# SignalBundling.net
KiCad netlist of a schematic drawn in Altium Designer
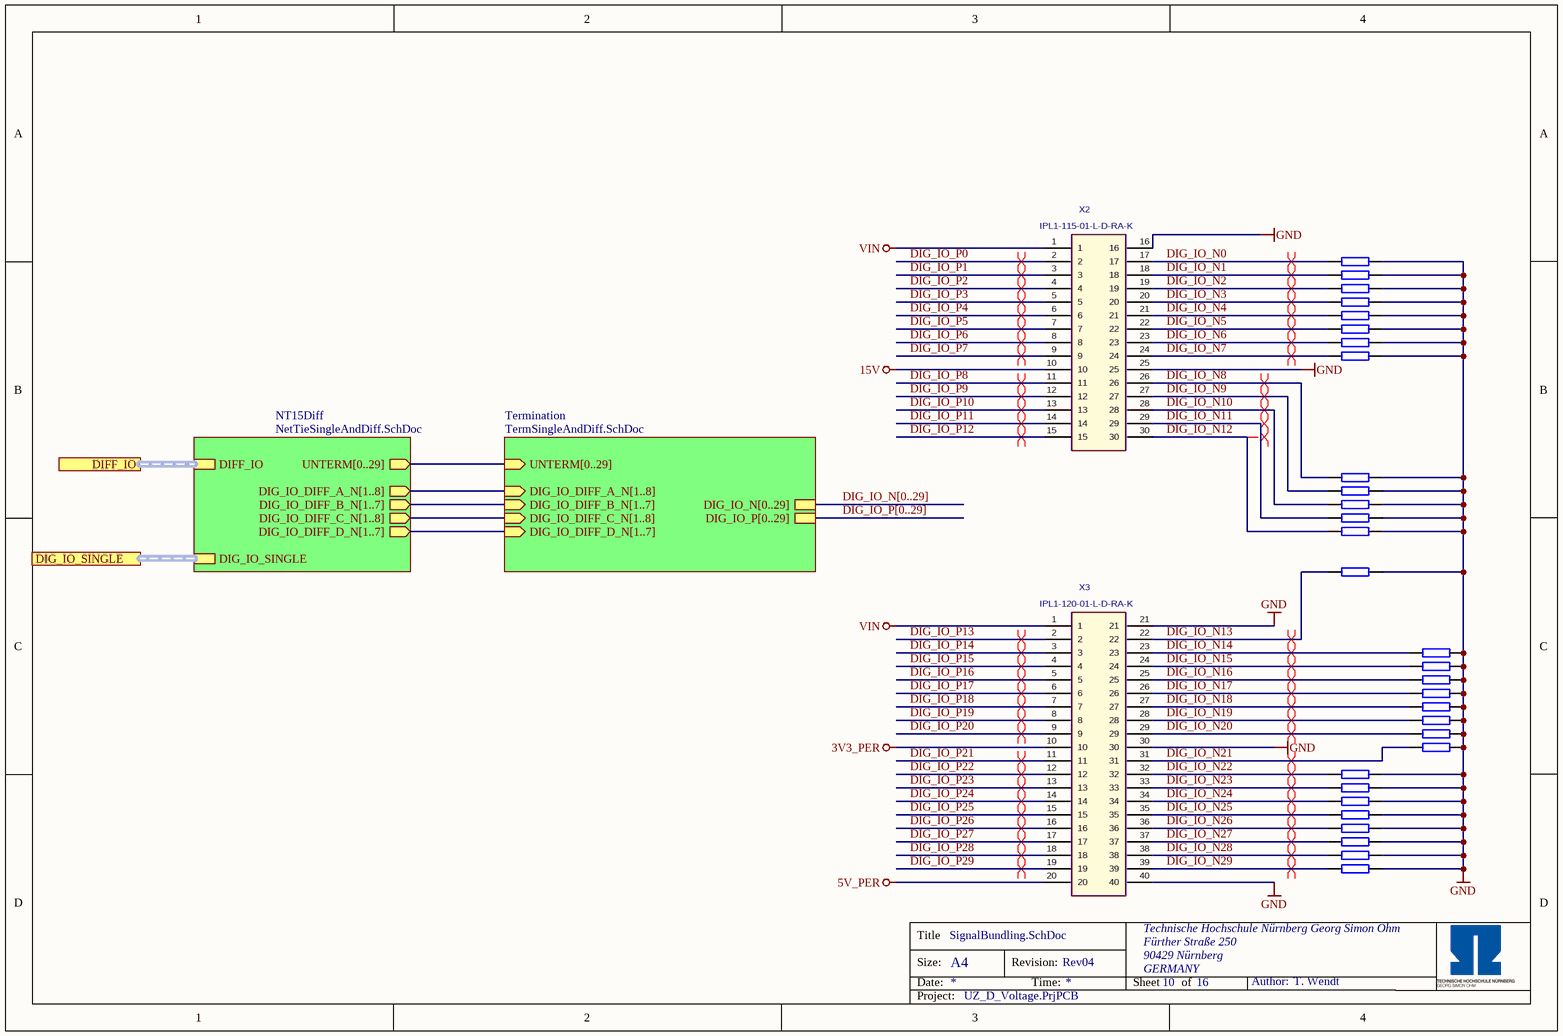
[diagram p0: SignalBundling.SchDoc]

(export (version "E")
  (design (tool "Eeschema 10.0.6"))
  (components
    (comp (ref "R21")
      (value "0R")
      (footprint "RES 0603_1608")
      (description "SMD resistor E24 series")
      (fields
        (field (name "MANUFACTURER PART NUMBER") "RC0603JR-070RL")
        (field (name "MANUFACTURER") "YAGEO")
        (field (name "CREATED FROM") "MGremer")
      )
      (libsource (lib "user") (part "Resistor"))
    )
    (comp (ref "R22")
      (value "0R")
      (footprint "RES 0603_1608")
      (description "SMD resistor E24 series")
      (fields
        (field (name "MANUFACTURER PART NUMBER") "RC0603JR-070RL")
        (field (name "MANUFACTURER") "YAGEO")
        (field (name "CREATED FROM") "MGremer")
      )
      (libsource (lib "user") (part "Resistor"))
    )
    (comp (ref "R23")
      (value "0R")
      (footprint "RES 0603_1608")
      (description "SMD resistor E24 series")
      (fields
        (field (name "MANUFACTURER PART NUMBER") "RC0603JR-070RL")
        (field (name "MANUFACTURER") "YAGEO")
        (field (name "CREATED FROM") "MGremer")
      )
      (libsource (lib "user") (part "Resistor"))
    )
    (comp (ref "R24")
      (value "0R")
      (footprint "RES 0603_1608")
      (description "SMD resistor E24 series")
      (fields
        (field (name "MANUFACTURER PART NUMBER") "RC0603JR-070RL")
        (field (name "MANUFACTURER") "YAGEO")
        (field (name "CREATED FROM") "MGremer")
      )
      (libsource (lib "user") (part "Resistor"))
    )
    (comp (ref "R25")
      (value "0R")
      (footprint "RES 0603_1608")
      (description "SMD resistor E24 series")
      (fields
        (field (name "MANUFACTURER PART NUMBER") "RC0603JR-070RL")
        (field (name "MANUFACTURER") "YAGEO")
        (field (name "CREATED FROM") "MGremer")
      )
      (libsource (lib "user") (part "Resistor"))
    )
    (comp (ref "R26")
      (value "0R")
      (footprint "RES 0603_1608")
      (description "SMD resistor E24 series")
      (fields
        (field (name "MANUFACTURER PART NUMBER") "RC0603JR-070RL")
        (field (name "MANUFACTURER") "YAGEO")
        (field (name "CREATED FROM") "MGremer")
      )
      (libsource (lib "user") (part "Resistor"))
    )
    (comp (ref "R27")
      (value "0R")
      (footprint "RES 0603_1608")
      (description "SMD resistor E24 series")
      (fields
        (field (name "MANUFACTURER PART NUMBER") "RC0603JR-070RL")
        (field (name "MANUFACTURER") "YAGEO")
        (field (name "CREATED FROM") "MGremer")
      )
      (libsource (lib "user") (part "Resistor"))
    )
    (comp (ref "R28")
      (value "0R")
      (footprint "RES 0603_1608")
      (description "SMD resistor E24 series")
      (fields
        (field (name "MANUFACTURER PART NUMBER") "RC0603JR-070RL")
        (field (name "MANUFACTURER") "YAGEO")
        (field (name "CREATED FROM") "MGremer")
      )
      (libsource (lib "user") (part "Resistor"))
    )
    (comp (ref "R29")
      (value "0R")
      (footprint "RES 0603_1608")
      (description "SMD resistor E24 series")
      (fields
        (field (name "MANUFACTURER PART NUMBER") "RC0603JR-070RL")
        (field (name "MANUFACTURER") "YAGEO")
        (field (name "CREATED FROM") "MGremer")
      )
      (libsource (lib "user") (part "Resistor"))
    )
    (comp (ref "R30")
      (value "0R")
      (footprint "RES 0603_1608")
      (description "SMD resistor E24 series")
      (fields
        (field (name "MANUFACTURER PART NUMBER") "RC0603JR-070RL")
        (field (name "MANUFACTURER") "YAGEO")
        (field (name "CREATED FROM") "MGremer")
      )
      (libsource (lib "user") (part "Resistor"))
    )
    (comp (ref "R31")
      (value "0R")
      (footprint "RES 0603_1608")
      (description "SMD resistor E24 series")
      (fields
        (field (name "MANUFACTURER PART NUMBER") "RC0603JR-070RL")
        (field (name "MANUFACTURER") "YAGEO")
        (field (name "CREATED FROM") "MGremer")
      )
      (libsource (lib "user") (part "Resistor"))
    )
    (comp (ref "R32")
      (value "0R")
      (footprint "RES 0603_1608")
      (description "SMD resistor E24 series")
      (fields
        (field (name "MANUFACTURER PART NUMBER") "RC0603JR-070RL")
        (field (name "MANUFACTURER") "YAGEO")
        (field (name "CREATED FROM") "MGremer")
      )
      (libsource (lib "user") (part "Resistor"))
    )
    (comp (ref "R33")
      (value "0R")
      (footprint "RES 0603_1608")
      (description "SMD resistor E24 series")
      (fields
        (field (name "MANUFACTURER PART NUMBER") "RC0603JR-070RL")
        (field (name "MANUFACTURER") "YAGEO")
        (field (name "CREATED FROM") "MGremer")
      )
      (libsource (lib "user") (part "Resistor"))
    )
    (comp (ref "R34")
      (value "0R")
      (footprint "RES 0603_1608")
      (description "SMD resistor E24 series")
      (fields
        (field (name "MANUFACTURER PART NUMBER") "RC0603JR-070RL")
        (field (name "MANUFACTURER") "YAGEO")
        (field (name "CREATED FROM") "MGremer")
      )
      (libsource (lib "user") (part "Resistor"))
    )
    (comp (ref "R35")
      (value "0R")
      (footprint "RES 0603_1608")
      (description "SMD resistor E24 series")
      (fields
        (field (name "MANUFACTURER PART NUMBER") "RC0603JR-070RL")
        (field (name "MANUFACTURER") "YAGEO")
        (field (name "CREATED FROM") "MGremer")
      )
      (libsource (lib "user") (part "Resistor"))
    )
    (comp (ref "R36")
      (value "0R")
      (footprint "RES 0603_1608")
      (description "SMD resistor E24 series")
      (fields
        (field (name "MANUFACTURER PART NUMBER") "RC0603JR-070RL")
        (field (name "MANUFACTURER") "YAGEO")
        (field (name "CREATED FROM") "MGremer")
      )
      (libsource (lib "user") (part "Resistor"))
    )
    (comp (ref "R37")
      (value "0R")
      (footprint "RES 0603_1608")
      (description "SMD resistor E24 series")
      (fields
        (field (name "MANUFACTURER PART NUMBER") "RC0603JR-070RL")
        (field (name "MANUFACTURER") "YAGEO")
        (field (name "CREATED FROM") "MGremer")
      )
      (libsource (lib "user") (part "Resistor"))
    )
    (comp (ref "R38")
      (value "0R")
      (footprint "RES 0603_1608")
      (description "SMD resistor E24 series")
      (fields
        (field (name "MANUFACTURER PART NUMBER") "RC0603JR-070RL")
        (field (name "MANUFACTURER") "YAGEO")
        (field (name "CREATED FROM") "MGremer")
      )
      (libsource (lib "user") (part "Resistor"))
    )
    (comp (ref "R39")
      (value "0R")
      (footprint "RES 0603_1608")
      (description "SMD resistor E24 series")
      (fields
        (field (name "MANUFACTURER PART NUMBER") "RC0603JR-070RL")
        (field (name "MANUFACTURER") "YAGEO")
        (field (name "CREATED FROM") "MGremer")
      )
      (libsource (lib "user") (part "Resistor"))
    )
    (comp (ref "R40")
      (value "0R")
      (footprint "RES 0603_1608")
      (description "SMD resistor E24 series")
      (fields
        (field (name "MANUFACTURER PART NUMBER") "RC0603JR-070RL")
        (field (name "MANUFACTURER") "YAGEO")
        (field (name "CREATED FROM") "MGremer")
      )
      (libsource (lib "user") (part "Resistor"))
    )
    (comp (ref "R41")
      (value "0R")
      (footprint "RES 0603_1608")
      (description "SMD resistor E24 series")
      (fields
        (field (name "MANUFACTURER PART NUMBER") "RC0603JR-070RL")
        (field (name "MANUFACTURER") "YAGEO")
        (field (name "CREATED FROM") "MGremer")
      )
      (libsource (lib "user") (part "Resistor"))
    )
    (comp (ref "R42")
      (value "0R")
      (footprint "RES 0603_1608")
      (description "SMD resistor E24 series")
      (fields
        (field (name "MANUFACTURER PART NUMBER") "RC0603JR-070RL")
        (field (name "MANUFACTURER") "YAGEO")
        (field (name "CREATED FROM") "MGremer")
      )
      (libsource (lib "user") (part "Resistor"))
    )
    (comp (ref "R43")
      (value "0R")
      (footprint "RES 0603_1608")
      (description "SMD resistor E24 series")
      (fields
        (field (name "MANUFACTURER PART NUMBER") "RC0603JR-070RL")
        (field (name "MANUFACTURER") "YAGEO")
        (field (name "CREATED FROM") "MGremer")
      )
      (libsource (lib "user") (part "Resistor"))
    )
    (comp (ref "R44")
      (value "0R")
      (footprint "RES 0603_1608")
      (description "SMD resistor E24 series")
      (fields
        (field (name "MANUFACTURER PART NUMBER") "RC0603JR-070RL")
        (field (name "MANUFACTURER") "YAGEO")
        (field (name "CREATED FROM") "MGremer")
      )
      (libsource (lib "user") (part "Resistor"))
    )
    (comp (ref "R45")
      (value "0R")
      (footprint "RES 0603_1608")
      (description "SMD resistor E24 series")
      (fields
        (field (name "MANUFACTURER PART NUMBER") "RC0603JR-070RL")
        (field (name "MANUFACTURER") "YAGEO")
        (field (name "CREATED FROM") "MGremer")
      )
      (libsource (lib "user") (part "Resistor"))
    )
    (comp (ref "R46")
      (value "0R")
      (footprint "RES 0603_1608")
      (description "SMD resistor E24 series")
      (fields
        (field (name "MANUFACTURER PART NUMBER") "RC0603JR-070RL")
        (field (name "MANUFACTURER") "YAGEO")
        (field (name "CREATED FROM") "MGremer")
      )
      (libsource (lib "user") (part "Resistor"))
    )
    (comp (ref "R47")
      (value "0R")
      (footprint "RES 0603_1608")
      (description "SMD resistor E24 series")
      (fields
        (field (name "MANUFACTURER PART NUMBER") "RC0603JR-070RL")
        (field (name "MANUFACTURER") "YAGEO")
        (field (name "CREATED FROM") "MGremer")
      )
      (libsource (lib "user") (part "Resistor"))
    )
    (comp (ref "R48")
      (value "0R")
      (footprint "RES 0603_1608")
      (description "SMD resistor E24 series")
      (fields
        (field (name "MANUFACTURER PART NUMBER") "RC0603JR-070RL")
        (field (name "MANUFACTURER") "YAGEO")
        (field (name "CREATED FROM") "MGremer")
      )
      (libsource (lib "user") (part "Resistor"))
    )
    (comp (ref "R49")
      (value "0R")
      (footprint "RES 0603_1608")
      (description "SMD resistor E24 series")
      (fields
        (field (name "MANUFACTURER PART NUMBER") "RC0603JR-070RL")
        (field (name "MANUFACTURER") "YAGEO")
        (field (name "CREATED FROM") "MGremer")
      )
      (libsource (lib "user") (part "Resistor"))
    )
    (comp (ref "R50")
      (value "0R")
      (footprint "RES 0603_1608")
      (description "SMD resistor E24 series")
      (fields
        (field (name "MANUFACTURER PART NUMBER") "RC0603JR-070RL")
        (field (name "MANUFACTURER") "YAGEO")
        (field (name "CREATED FROM") "MGremer")
      )
      (libsource (lib "user") (part "Resistor"))
    )
    (comp (ref "X2")
      (value "IPL1-115-01-L-D-RA-K")
      (footprint "IPL1-115-01-XX-D-RA")
      (description "Terminal Assembly, Double Row, Right Angle, Thru-Hole, 2.54 mm x 2.54 mm Pitch, 30 Pins")
      (fields (field (name "MANUFACTURER") "SAMTEC") (field (name "CREATED FROM") "TWendt"))
      (libsource (lib "user") (part "IPL1-115-01-XX-D-RA"))
    )
    (comp (ref "X3")
      (value "IPL1-120-01-L-D-RA-K")
      (footprint "IPL1-120-01-XX-D-RA")
      (description "Terminal Assembly, Double Row, Right Angle, Thru-Hole, 2.54 mm x 2.54 mm Pitch, 40 Pins")
      (fields (field (name "MANUFACTURER") "SAMTEC") (field (name "CREATED FROM") "TWendt"))
      (libsource (lib "user") (part "IPL1-120-01-XX-D-RA"))
    )
  )
  (nets
    (net (code "8") (name "/DIG_IO_N0") (class "Default")
      (node (ref "R21") (pin "1") (pinfunction "1_1") (pintype "passive"))
      (node (ref "X2") (pin "17") (pinfunction "17_17") (pintype "passive"))
    )
    (net (code "9") (name "/DIG_IO_N1") (class "Default")
      (node (ref "R22") (pin "1") (pinfunction "1_1") (pintype "passive"))
      (node (ref "X2") (pin "18") (pinfunction "18_18") (pintype "passive"))
    )
    (net (code "10") (name "/DIG_IO_N2") (class "Default")
      (node (ref "R23") (pin "1") (pinfunction "1_1") (pintype "passive"))
      (node (ref "X2") (pin "19") (pinfunction "19_19") (pintype "passive"))
    )
    (net (code "11") (name "/DIG_IO_N3") (class "Default")
      (node (ref "R24") (pin "1") (pinfunction "1_1") (pintype "passive"))
      (node (ref "X2") (pin "20") (pinfunction "20_20") (pintype "passive"))
    )
    (net (code "12") (name "/DIG_IO_N4") (class "Default")
      (node (ref "R25") (pin "1") (pinfunction "1_1") (pintype "passive"))
      (node (ref "X2") (pin "21") (pinfunction "21_21") (pintype "passive"))
    )
    (net (code "13") (name "/DIG_IO_N5") (class "Default")
      (node (ref "R26") (pin "1") (pinfunction "1_1") (pintype "passive"))
      (node (ref "X2") (pin "22") (pinfunction "22_22") (pintype "passive"))
    )
    (net (code "14") (name "/DIG_IO_N6") (class "Default")
      (node (ref "R27") (pin "1") (pinfunction "1_1") (pintype "passive"))
      (node (ref "X2") (pin "23") (pinfunction "23_23") (pintype "passive"))
    )
    (net (code "15") (name "/DIG_IO_N7") (class "Default")
      (node (ref "R28") (pin "1") (pinfunction "1_1") (pintype "passive"))
      (node (ref "X2") (pin "24") (pinfunction "24_24") (pintype "passive"))
    )
    (net (code "16") (name "/DIG_IO_N8") (class "Default")
      (node (ref "R29") (pin "1") (pinfunction "1_1") (pintype "passive"))
      (node (ref "X2") (pin "26") (pinfunction "26_26") (pintype "passive"))
    )
    (net (code "17") (name "/DIG_IO_N9") (class "Default")
      (node (ref "R30") (pin "1") (pinfunction "1_1") (pintype "passive"))
      (node (ref "X2") (pin "27") (pinfunction "27_27") (pintype "passive"))
    )
    (net (code "18") (name "/DIG_IO_N10") (class "Default")
      (node (ref "R31") (pin "1") (pinfunction "1_1") (pintype "passive"))
      (node (ref "X2") (pin "28") (pinfunction "28_28") (pintype "passive"))
    )
    (net (code "19") (name "/DIG_IO_N11") (class "Default")
      (node (ref "R32") (pin "1") (pinfunction "1_1") (pintype "passive"))
      (node (ref "X2") (pin "29") (pinfunction "29_29") (pintype "passive"))
    )
    (net (code "20") (name "/DIG_IO_N12") (class "Default")
      (node (ref "R33") (pin "1") (pinfunction "1_1") (pintype "passive"))
      (node (ref "X2") (pin "30") (pinfunction "30_30") (pintype "passive"))
    )
    (net (code "21") (name "/DIG_IO_N13") (class "Default")
      (node (ref "R34") (pin "1") (pinfunction "1_1") (pintype "passive"))
      (node (ref "X3") (pin "22") (pinfunction "22_22") (pintype "passive"))
    )
    (net (code "22") (name "/DIG_IO_N14") (class "Default")
      (node (ref "R35") (pin "1") (pinfunction "1_1") (pintype "passive"))
      (node (ref "X3") (pin "23") (pinfunction "23_23") (pintype "passive"))
    )
    (net (code "23") (name "/DIG_IO_N15") (class "Default")
      (node (ref "R36") (pin "1") (pinfunction "1_1") (pintype "passive"))
      (node (ref "X3") (pin "24") (pinfunction "24_24") (pintype "passive"))
    )
    (net (code "24") (name "/DIG_IO_N16") (class "Default")
      (node (ref "R37") (pin "1") (pinfunction "1_1") (pintype "passive"))
      (node (ref "X3") (pin "25") (pinfunction "25_25") (pintype "passive"))
    )
    (net (code "25") (name "/DIG_IO_N17") (class "Default")
      (node (ref "R38") (pin "1") (pinfunction "1_1") (pintype "passive"))
      (node (ref "X3") (pin "26") (pinfunction "26_26") (pintype "passive"))
    )
    (net (code "26") (name "/DIG_IO_N18") (class "Default")
      (node (ref "R39") (pin "1") (pinfunction "1_1") (pintype "passive"))
      (node (ref "X3") (pin "27") (pinfunction "27_27") (pintype "passive"))
    )
    (net (code "27") (name "/DIG_IO_N19") (class "Default")
      (node (ref "R40") (pin "1") (pinfunction "1_1") (pintype "passive"))
      (node (ref "X3") (pin "28") (pinfunction "28_28") (pintype "passive"))
    )
    (net (code "28") (name "/DIG_IO_N20") (class "Default")
      (node (ref "R41") (pin "1") (pinfunction "1_1") (pintype "passive"))
      (node (ref "X3") (pin "29") (pinfunction "29_29") (pintype "passive"))
    )
    (net (code "29") (name "/DIG_IO_N21") (class "Default")
      (node (ref "R42") (pin "1") (pinfunction "1_1") (pintype "passive"))
      (node (ref "X3") (pin "31") (pinfunction "31_31") (pintype "passive"))
    )
    (net (code "30") (name "/DIG_IO_N22") (class "Default")
      (node (ref "R43") (pin "1") (pinfunction "1_1") (pintype "passive"))
      (node (ref "X3") (pin "32") (pinfunction "32_32") (pintype "passive"))
    )
    (net (code "31") (name "/DIG_IO_N23") (class "Default")
      (node (ref "R44") (pin "1") (pinfunction "1_1") (pintype "passive"))
      (node (ref "X3") (pin "33") (pinfunction "33_33") (pintype "passive"))
    )
    (net (code "32") (name "/DIG_IO_N24") (class "Default")
      (node (ref "R45") (pin "1") (pinfunction "1_1") (pintype "passive"))
      (node (ref "X3") (pin "34") (pinfunction "34_34") (pintype "passive"))
    )
    (net (code "33") (name "/DIG_IO_N25") (class "Default")
      (node (ref "R46") (pin "1") (pinfunction "1_1") (pintype "passive"))
      (node (ref "X3") (pin "35") (pinfunction "35_35") (pintype "passive"))
    )
    (net (code "34") (name "/DIG_IO_N26") (class "Default")
      (node (ref "R47") (pin "1") (pinfunction "1_1") (pintype "passive"))
      (node (ref "X3") (pin "36") (pinfunction "36_36") (pintype "passive"))
    )
    (net (code "35") (name "/DIG_IO_N27") (class "Default")
      (node (ref "R48") (pin "1") (pinfunction "1_1") (pintype "passive"))
      (node (ref "X3") (pin "37") (pinfunction "37_37") (pintype "passive"))
    )
    (net (code "36") (name "/DIG_IO_N28") (class "Default")
      (node (ref "R49") (pin "1") (pinfunction "1_1") (pintype "passive"))
      (node (ref "X3") (pin "38") (pinfunction "38_38") (pintype "passive"))
    )
    (net (code "37") (name "/DIG_IO_N29") (class "Default")
      (node (ref "R50") (pin "1") (pinfunction "1_1") (pintype "passive"))
      (node (ref "X3") (pin "39") (pinfunction "39_39") (pintype "passive"))
    )
    (net (code "39") (name "/DIG_IO_P0") (class "Default")
      (node (ref "X2") (pin "2") (pinfunction "2_2") (pintype "passive"))
    )
    (net (code "40") (name "/DIG_IO_P1") (class "Default")
      (node (ref "X2") (pin "3") (pinfunction "3_3") (pintype "passive"))
    )
    (net (code "41") (name "/DIG_IO_P2") (class "Default")
      (node (ref "X2") (pin "4") (pinfunction "4_4") (pintype "passive"))
    )
    (net (code "42") (name "/DIG_IO_P3") (class "Default")
      (node (ref "X2") (pin "5") (pinfunction "5_5") (pintype "passive"))
    )
    (net (code "43") (name "/DIG_IO_P4") (class "Default")
      (node (ref "X2") (pin "6") (pinfunction "6_6") (pintype "passive"))
    )
    (net (code "44") (name "/DIG_IO_P5") (class "Default")
      (node (ref "X2") (pin "7") (pinfunction "7_7") (pintype "passive"))
    )
    (net (code "45") (name "/DIG_IO_P6") (class "Default")
      (node (ref "X2") (pin "8") (pinfunction "8_8") (pintype "passive"))
    )
    (net (code "46") (name "/DIG_IO_P7") (class "Default")
      (node (ref "X2") (pin "9") (pinfunction "9_9") (pintype "passive"))
    )
    (net (code "47") (name "/DIG_IO_P8") (class "Default")
      (node (ref "X2") (pin "11") (pinfunction "11_11") (pintype "passive"))
    )
    (net (code "48") (name "/DIG_IO_P9") (class "Default")
      (node (ref "X2") (pin "12") (pinfunction "12_12") (pintype "passive"))
    )
    (net (code "49") (name "/DIG_IO_P10") (class "Default")
      (node (ref "X2") (pin "13") (pinfunction "13_13") (pintype "passive"))
    )
    (net (code "50") (name "/DIG_IO_P11") (class "Default")
      (node (ref "X2") (pin "14") (pinfunction "14_14") (pintype "passive"))
    )
    (net (code "51") (name "/DIG_IO_P12") (class "Default")
      (node (ref "X2") (pin "15") (pinfunction "15_15") (pintype "passive"))
    )
    (net (code "52") (name "/DIG_IO_P13") (class "Default")
      (node (ref "X3") (pin "2") (pinfunction "2_2") (pintype "passive"))
    )
    (net (code "53") (name "/DIG_IO_P14") (class "Default")
      (node (ref "X3") (pin "3") (pinfunction "3_3") (pintype "passive"))
    )
    (net (code "54") (name "/DIG_IO_P15") (class "Default")
      (node (ref "X3") (pin "4") (pinfunction "4_4") (pintype "passive"))
    )
    (net (code "55") (name "/DIG_IO_P16") (class "Default")
      (node (ref "X3") (pin "5") (pinfunction "5_5") (pintype "passive"))
    )
    (net (code "56") (name "/DIG_IO_P17") (class "Default")
      (node (ref "X3") (pin "6") (pinfunction "6_6") (pintype "passive"))
    )
    (net (code "57") (name "/DIG_IO_P18") (class "Default")
      (node (ref "X3") (pin "7") (pinfunction "7_7") (pintype "passive"))
    )
    (net (code "58") (name "/DIG_IO_P19") (class "Default")
      (node (ref "X3") (pin "8") (pinfunction "8_8") (pintype "passive"))
    )
    (net (code "59") (name "/DIG_IO_P20") (class "Default")
      (node (ref "X3") (pin "9") (pinfunction "9_9") (pintype "passive"))
    )
    (net (code "60") (name "/DIG_IO_P21") (class "Default")
      (node (ref "X3") (pin "11") (pinfunction "11_11") (pintype "passive"))
    )
    (net (code "61") (name "/DIG_IO_P22") (class "Default")
      (node (ref "X3") (pin "12") (pinfunction "12_12") (pintype "passive"))
    )
    (net (code "62") (name "/DIG_IO_P23") (class "Default")
      (node (ref "X3") (pin "13") (pinfunction "13_13") (pintype "passive"))
    )
    (net (code "63") (name "/DIG_IO_P24") (class "Default")
      (node (ref "X3") (pin "14") (pinfunction "14_14") (pintype "passive"))
    )
    (net (code "64") (name "/DIG_IO_P25") (class "Default")
      (node (ref "X3") (pin "15") (pinfunction "15_15") (pintype "passive"))
    )
    (net (code "65") (name "/DIG_IO_P26") (class "Default")
      (node (ref "X3") (pin "16") (pinfunction "16_16") (pintype "passive"))
    )
    (net (code "66") (name "/DIG_IO_P27") (class "Default")
      (node (ref "X3") (pin "17") (pinfunction "17_17") (pintype "passive"))
    )
    (net (code "67") (name "/DIG_IO_P28") (class "Default")
      (node (ref "X3") (pin "18") (pinfunction "18_18") (pintype "passive"))
    )
    (net (code "68") (name "/DIG_IO_P29") (class "Default")
      (node (ref "X3") (pin "19") (pinfunction "19_19") (pintype "passive"))
    )
    (net (code "72") (name "3V3_PER") (class "Default")
      (node (ref "X3") (pin "10") (pinfunction "10_10") (pintype "passive"))
    )
    (net (code "73") (name "5V_PER") (class "Default")
      (node (ref "X3") (pin "20") (pinfunction "20_20") (pintype "passive"))
    )
    (net (code "74") (name "15V") (class "Default")
      (node (ref "X2") (pin "10") (pinfunction "10_10") (pintype "passive"))
    )
    (net (code "75") (name "GND") (class "Default")
      (node (ref "R21") (pin "2") (pinfunction "2_2") (pintype "passive"))
      (node (ref "R22") (pin "2") (pinfunction "2_2") (pintype "passive"))
      (node (ref "R23") (pin "2") (pinfunction "2_2") (pintype "passive"))
      (node (ref "R24") (pin "2") (pinfunction "2_2") (pintype "passive"))
      (node (ref "R25") (pin "2") (pinfunction "2_2") (pintype "passive"))
      (node (ref "R26") (pin "2") (pinfunction "2_2") (pintype "passive"))
      (node (ref "R27") (pin "2") (pinfunction "2_2") (pintype "passive"))
      (node (ref "R28") (pin "2") (pinfunction "2_2") (pintype "passive"))
      (node (ref "R29") (pin "2") (pinfunction "2_2") (pintype "passive"))
      (node (ref "R30") (pin "2") (pinfunction "2_2") (pintype "passive"))
      (node (ref "R31") (pin "2") (pinfunction "2_2") (pintype "passive"))
      (node (ref "R32") (pin "2") (pinfunction "2_2") (pintype "passive"))
      (node (ref "R33") (pin "2") (pinfunction "2_2") (pintype "passive"))
      (node (ref "R34") (pin "2") (pinfunction "2_2") (pintype "passive"))
      (node (ref "R35") (pin "2") (pinfunction "2_2") (pintype "passive"))
      (node (ref "R36") (pin "2") (pinfunction "2_2") (pintype "passive"))
      (node (ref "R37") (pin "2") (pinfunction "2_2") (pintype "passive"))
      (node (ref "R38") (pin "2") (pinfunction "2_2") (pintype "passive"))
      (node (ref "R39") (pin "2") (pinfunction "2_2") (pintype "passive"))
      (node (ref "R40") (pin "2") (pinfunction "2_2") (pintype "passive"))
      (node (ref "R41") (pin "2") (pinfunction "2_2") (pintype "passive"))
      (node (ref "R42") (pin "2") (pinfunction "2_2") (pintype "passive"))
      (node (ref "R43") (pin "2") (pinfunction "2_2") (pintype "passive"))
      (node (ref "R44") (pin "2") (pinfunction "2_2") (pintype "passive"))
      (node (ref "R45") (pin "2") (pinfunction "2_2") (pintype "passive"))
      (node (ref "R46") (pin "2") (pinfunction "2_2") (pintype "passive"))
      (node (ref "R47") (pin "2") (pinfunction "2_2") (pintype "passive"))
      (node (ref "R48") (pin "2") (pinfunction "2_2") (pintype "passive"))
      (node (ref "R49") (pin "2") (pinfunction "2_2") (pintype "passive"))
      (node (ref "R50") (pin "2") (pinfunction "2_2") (pintype "passive"))
      (node (ref "X2") (pin "16") (pinfunction "16_16") (pintype "passive"))
      (node (ref "X2") (pin "25") (pinfunction "25_25") (pintype "passive"))
      (node (ref "X3") (pin "21") (pinfunction "21_21") (pintype "passive"))
      (node (ref "X3") (pin "30") (pinfunction "30_30") (pintype "passive"))
      (node (ref "X3") (pin "40") (pinfunction "40_40") (pintype "passive"))
    )
    (net (code "76") (name "VIN") (class "Default")
      (node (ref "X2") (pin "1") (pinfunction "1_1") (pintype "passive"))
      (node (ref "X3") (pin "1") (pinfunction "1_1") (pintype "passive"))
    )
  )
)
